# Placa_de_Baixo.net
KiCad netlist of a schematic drawn in EAGLE
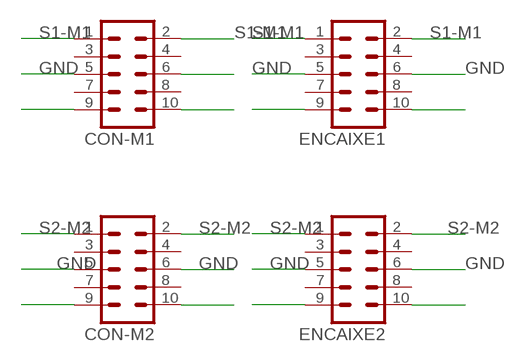
[diagram p0: schematic, sheet 1]

(export (version "E")
  (design (tool "Eeschema 10.0.6"))
  (components
    (comp (ref "CON-M1")
      (value "MA05-2")
      (footprint "eagle-import:MA05-2")
      (libsource (lib "eagle-import") (part "MA05-2"))
    )
    (comp (ref "CON-M2")
      (value "MA05-2")
      (footprint "eagle-import:MA05-2")
      (libsource (lib "eagle-import") (part "MA05-2"))
    )
    (comp (ref "ENCAIXE1")
      (value "ML10L")
      (footprint "eagle-import:ML10L")
      (libsource (lib "eagle-import") (part "ML10L"))
    )
    (comp (ref "ENCAIXE2")
      (value "ML10L")
      (footprint "eagle-import:ML10L")
      (libsource (lib "eagle-import") (part "ML10L"))
    )
  )
  (nets
    (net (code "1") (name "/COMANDO-1") (class "Default")
      (node (ref "CON-M1") (pin "9") (pinfunction "9_9") (pintype "passive"))
      (node (ref "ENCAIXE1") (pin "10") (pinfunction "10_10") (pintype "passive"))
    )
    (net (code "2") (name "/COMANDO-2") (class "Default")
      (node (ref "CON-M1") (pin "10") (pinfunction "10_10") (pintype "passive"))
      (node (ref "ENCAIXE1") (pin "9") (pinfunction "9_9") (pintype "passive"))
    )
    (net (code "3") (name "/COMANDO-A") (class "Default")
      (node (ref "CON-M2") (pin "9") (pinfunction "9_9") (pintype "passive"))
      (node (ref "ENCAIXE2") (pin "10") (pinfunction "10_10") (pintype "passive"))
    )
    (net (code "4") (name "/COMANDO-B") (class "Default")
      (node (ref "CON-M2") (pin "10") (pinfunction "10_10") (pintype "passive"))
      (node (ref "ENCAIXE2") (pin "9") (pinfunction "9_9") (pintype "passive"))
    )
    (net (code "5") (name "/GND") (class "Default")
      (node (ref "CON-M1") (pin "5") (pinfunction "5_5") (pintype "passive"))
      (node (ref "CON-M1") (pin "6") (pinfunction "6_6") (pintype "passive"))
      (node (ref "CON-M2") (pin "5") (pinfunction "5_5") (pintype "passive"))
      (node (ref "CON-M2") (pin "6") (pinfunction "6_6") (pintype "passive"))
      (node (ref "ENCAIXE1") (pin "5") (pinfunction "5_5") (pintype "passive"))
      (node (ref "ENCAIXE1") (pin "6") (pinfunction "6_6") (pintype "passive"))
      (node (ref "ENCAIXE2") (pin "5") (pinfunction "5_5") (pintype "passive"))
      (node (ref "ENCAIXE2") (pin "6") (pinfunction "6_6") (pintype "passive"))
    )
    (net (code "6") (name "/S1-M1") (class "Default")
      (node (ref "CON-M1") (pin "1") (pinfunction "1_1") (pintype "passive"))
      (node (ref "CON-M1") (pin "2") (pinfunction "2_2") (pintype "passive"))
      (node (ref "ENCAIXE1") (pin "1") (pinfunction "1_1") (pintype "passive"))
      (node (ref "ENCAIXE1") (pin "2") (pinfunction "2_2") (pintype "passive"))
    )
    (net (code "7") (name "/S2-M2") (class "Default")
      (node (ref "CON-M2") (pin "1") (pinfunction "1_1") (pintype "passive"))
      (node (ref "CON-M2") (pin "2") (pinfunction "2_2") (pintype "passive"))
      (node (ref "ENCAIXE2") (pin "1") (pinfunction "1_1") (pintype "passive"))
      (node (ref "ENCAIXE2") (pin "2") (pinfunction "2_2") (pintype "passive"))
    )
    (net (code "8") (name "unconnected-(CON-M1-Pad3)") (class "Default")
      (node (ref "CON-M1") (pin "3") (pinfunction "3_3") (pintype "passive"))
    )
    (net (code "9") (name "unconnected-(CON-M1-Pad4)") (class "Default")
      (node (ref "CON-M1") (pin "4") (pinfunction "4_4") (pintype "passive"))
    )
    (net (code "10") (name "unconnected-(CON-M1-Pad7)") (class "Default")
      (node (ref "CON-M1") (pin "7") (pinfunction "7_7") (pintype "passive"))
    )
    (net (code "11") (name "unconnected-(CON-M1-Pad8)") (class "Default")
      (node (ref "CON-M1") (pin "8") (pinfunction "8_8") (pintype "passive"))
    )
    (net (code "12") (name "unconnected-(CON-M2-Pad3)") (class "Default")
      (node (ref "CON-M2") (pin "3") (pinfunction "3_3") (pintype "passive"))
    )
    (net (code "13") (name "unconnected-(CON-M2-Pad4)") (class "Default")
      (node (ref "CON-M2") (pin "4") (pinfunction "4_4") (pintype "passive"))
    )
    (net (code "14") (name "unconnected-(CON-M2-Pad7)") (class "Default")
      (node (ref "CON-M2") (pin "7") (pinfunction "7_7") (pintype "passive"))
    )
    (net (code "15") (name "unconnected-(CON-M2-Pad8)") (class "Default")
      (node (ref "CON-M2") (pin "8") (pinfunction "8_8") (pintype "passive"))
    )
    (net (code "16") (name "unconnected-(ENCAIXE1-Pad3)") (class "Default")
      (node (ref "ENCAIXE1") (pin "3") (pinfunction "3_3") (pintype "passive"))
    )
    (net (code "17") (name "unconnected-(ENCAIXE1-Pad4)") (class "Default")
      (node (ref "ENCAIXE1") (pin "4") (pinfunction "4_4") (pintype "passive"))
    )
    (net (code "18") (name "unconnected-(ENCAIXE1-Pad7)") (class "Default")
      (node (ref "ENCAIXE1") (pin "7") (pinfunction "7_7") (pintype "passive"))
    )
    (net (code "19") (name "unconnected-(ENCAIXE1-Pad8)") (class "Default")
      (node (ref "ENCAIXE1") (pin "8") (pinfunction "8_8") (pintype "passive"))
    )
    (net (code "20") (name "unconnected-(ENCAIXE2-Pad3)") (class "Default")
      (node (ref "ENCAIXE2") (pin "3") (pinfunction "3_3") (pintype "passive"))
    )
    (net (code "21") (name "unconnected-(ENCAIXE2-Pad4)") (class "Default")
      (node (ref "ENCAIXE2") (pin "4") (pinfunction "4_4") (pintype "passive"))
    )
    (net (code "22") (name "unconnected-(ENCAIXE2-Pad7)") (class "Default")
      (node (ref "ENCAIXE2") (pin "7") (pinfunction "7_7") (pintype "passive"))
    )
    (net (code "23") (name "unconnected-(ENCAIXE2-Pad8)") (class "Default")
      (node (ref "ENCAIXE2") (pin "8") (pinfunction "8_8") (pintype "passive"))
    )
  )
)
